# PortableShower.net
KiCad netlist of a schematic drawn in EAGLE
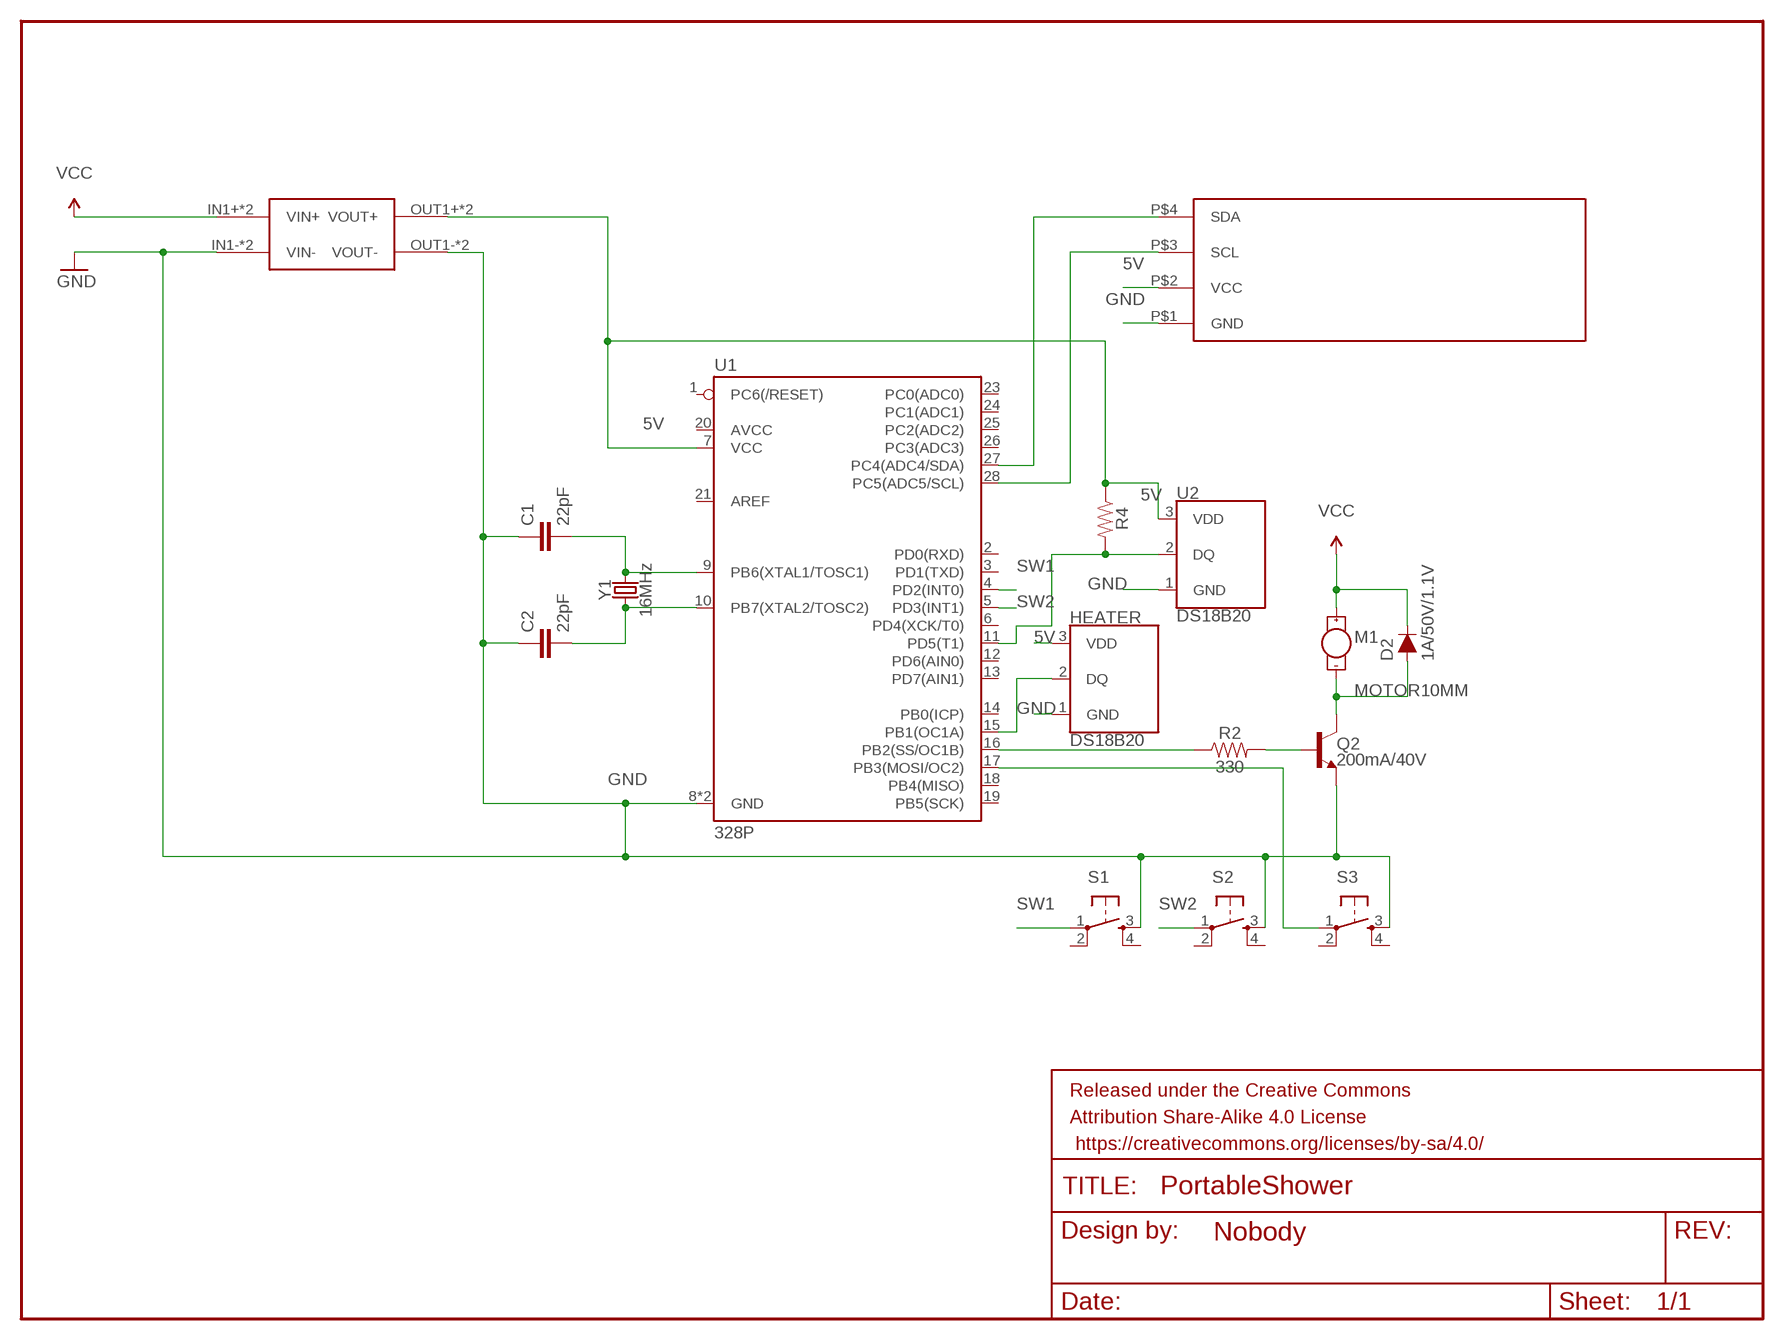
[diagram p0: schematic, sheet 1]

(export (version "E")
  (design (tool "Eeschema 10.0.6"))
  (components
    (comp (ref "C1")
      (value "22pF")
      (footprint "eagle-import:CAP-PTH-2.54")
      (libsource (lib "eagle-import") (part "22PF-PTH-2.54MM-200V-5%"))
    )
    (comp (ref "C2")
      (value "22pF")
      (footprint "eagle-import:CAP-PTH-2.54")
      (libsource (lib "eagle-import") (part "22PF-PTH-2.54MM-200V-5%"))
    )
    (comp (ref "D2")
      (value "1A/50V/1.1V")
      (footprint "eagle-import:DIODE-1N4001")
      (libsource (lib "eagle-import") (part "DIODE-PTH"))
    )
    (comp (ref "FRAME1")
      (value "FRAME-LETTERNO_PACKAGE")
      (footprint "eagle-import:DUMMY")
      (fields (field (name "DESIGNER") "Nobody"))
      (libsource (lib "eagle-import") (part "FRAME-LETTERNO_PACKAGE"))
    )
    (comp (ref "HEATER")
      (value "DS18B20")
      (footprint "eagle-import:TO-92-AMMO")
      (libsource (lib "eagle-import") (part "DS18B20"))
    )
    (comp (ref "M1")
      (value "MOTOR10MM")
      (footprint "eagle-import:VIBE-MOTOR-10MM")
      (libsource (lib "eagle-import") (part "MOTOR10MM"))
    )
    (comp (ref "OLED")
      (value "OLED")
      (footprint "eagle-import:SIP")
      (libsource (lib "eagle-import") (part "OLED"))
    )
    (comp (ref "Q2")
      (value "200mA/40V")
      (footprint "eagle-import:TO-92")
      (libsource (lib "eagle-import") (part "TRANS_NPN-2N3904"))
    )
    (comp (ref "R2")
      (value "330")
      (footprint "eagle-import:AXIAL-0.3")
      (libsource (lib "eagle-import") (part "330OHM-HORIZ-1/10W-5%"))
    )
    (comp (ref "R4")
      (value "RESISTORAXIAL-0.3")
      (footprint "eagle-import:AXIAL-0.3")
      (libsource (lib "eagle-import") (part "RESISTORAXIAL-0.3"))
    )
    (comp (ref "S1")
      (value "TAC_SWITCHPTH")
      (footprint "eagle-import:TACTILE-PTH")
      (libsource (lib "eagle-import") (part "TAC_SWITCHPTH"))
    )
    (comp (ref "S2")
      (value "TAC_SWITCHPTH")
      (footprint "eagle-import:TACTILE-PTH")
      (libsource (lib "eagle-import") (part "TAC_SWITCHPTH"))
    )
    (comp (ref "S3")
      (value "TAC_SWITCHPTH")
      (footprint "eagle-import:TACTILE-PTH")
      (libsource (lib "eagle-import") (part "TAC_SWITCHPTH"))
    )
    (comp (ref "U$1")
      (value "MP1584")
      (footprint "eagle-import:DC-BRICK")
      (libsource (lib "eagle-import") (part "MP1584"))
    )
    (comp (ref "U1")
      (value "328P")
      (footprint "eagle-import:DIP28")
      (libsource (lib "eagle-import") (part "ATMEGA328P_PDIP"))
    )
    (comp (ref "U2")
      (value "DS18B20")
      (footprint "eagle-import:TO-92-AMMO")
      (libsource (lib "eagle-import") (part "DS18B20"))
    )
    (comp (ref "Y1")
      (value "16MHz")
      (footprint "eagle-import:HC49US")
      (libsource (lib "eagle-import") (part "CRYSTAL-16MHZPTH-HC49US"))
    )
  )
  (nets
    (net (code "1") (name "/5V") (class "Default")
      (node (ref "HEATER") (pin "3") (pinfunction "VDD_3") (pintype "power_in"))
      (node (ref "OLED") (pin "P$2") (pinfunction "VCC_P$2") (pintype "bidirectional"))
      (node (ref "R4") (pin "P$1") (pinfunction "1_P$1") (pintype "passive"))
      (node (ref "U$1") (pin "OUT1+") (pinfunction "VOUT+_OUT1+") (pintype "output"))
      (node (ref "U$1") (pin "OUT2+") (pinfunction "VOUT+_OUT2+") (pintype "output"))
      (node (ref "U1") (pin "7") (pinfunction "VCC_7") (pintype "bidirectional"))
      (node (ref "U2") (pin "3") (pinfunction "VDD_3") (pintype "power_in"))
    )
    (net (code "2") (name "/SW1") (class "Default")
      (node (ref "S1") (pin "1") (pinfunction "1_1") (pintype "passive"))
      (node (ref "U1") (pin "4") (pinfunction "PD2(INT0)_4") (pintype "bidirectional"))
    )
    (net (code "3") (name "/SW2") (class "Default")
      (node (ref "S2") (pin "1") (pinfunction "1_1") (pintype "passive"))
      (node (ref "U1") (pin "5") (pinfunction "PD3(INT1)_5") (pintype "bidirectional"))
    )
    (net (code "4") (name "GND") (class "Default")
      (node (ref "C1") (pin "1") (pinfunction "1_1") (pintype "passive"))
      (node (ref "C2") (pin "1") (pinfunction "1_1") (pintype "passive"))
      (node (ref "HEATER") (pin "1") (pinfunction "GND_1") (pintype "power_in"))
      (node (ref "OLED") (pin "P$1") (pinfunction "GND_P$1") (pintype "bidirectional"))
      (node (ref "Q2") (pin "1") (pinfunction "E_1") (pintype "passive"))
      (node (ref "S1") (pin "3") (pinfunction "3_3") (pintype "passive"))
      (node (ref "S2") (pin "3") (pinfunction "3_3") (pintype "passive"))
      (node (ref "S3") (pin "3") (pinfunction "3_3") (pintype "passive"))
      (node (ref "U$1") (pin "IN1-") (pinfunction "VIN-_IN1-") (pintype "input"))
      (node (ref "U$1") (pin "IN2-") (pinfunction "VIN-_IN2-") (pintype "input"))
      (node (ref "U$1") (pin "OUT1-") (pinfunction "VOUT-_OUT1-") (pintype "output"))
      (node (ref "U$1") (pin "OUT2-") (pinfunction "VOUT-_OUT2-") (pintype "output"))
      (node (ref "U1") (pin "22") (pinfunction "GND_22") (pintype "bidirectional"))
      (node (ref "U1") (pin "8") (pinfunction "GND_8") (pintype "bidirectional"))
      (node (ref "U2") (pin "1") (pinfunction "GND_1") (pintype "power_in"))
    )
    (net (code "5") (name "Net-(HEATER-DQ)") (class "Default")
      (node (ref "HEATER") (pin "2") (pinfunction "DQ_2") (pintype "bidirectional"))
      (node (ref "U1") (pin "15") (pinfunction "PB1(OC1A)_15") (pintype "bidirectional"))
    )
    (net (code "6") (name "Net-(OLED-SCL)") (class "Default")
      (node (ref "OLED") (pin "P$3") (pinfunction "SCL_P$3") (pintype "bidirectional"))
      (node (ref "U1") (pin "28") (pinfunction "PC5(ADC5/SCL)_28") (pintype "bidirectional"))
    )
    (net (code "7") (name "Net-(OLED-SDA)") (class "Default")
      (node (ref "OLED") (pin "P$4") (pinfunction "SDA_P$4") (pintype "bidirectional"))
      (node (ref "U1") (pin "27") (pinfunction "PC4(ADC4/SDA)_27") (pintype "bidirectional"))
    )
    (net (code "8") (name "Net-(Q2-B)") (class "Default")
      (node (ref "Q2") (pin "2") (pinfunction "B_2") (pintype "passive"))
      (node (ref "R2") (pin "P$2") (pinfunction "2_P$2") (pintype "passive"))
    )
    (net (code "9") (name "Net-(Q2-C)") (class "Default")
      (node (ref "D2") (pin "A") (pinfunction "A_A") (pintype "passive"))
      (node (ref "M1") (pin "-") (pinfunction "-_-") (pintype "bidirectional"))
      (node (ref "Q2") (pin "3") (pinfunction "C_3") (pintype "passive"))
    )
    (net (code "10") (name "Net-(R2-1)") (class "Default")
      (node (ref "R2") (pin "P$1") (pinfunction "1_P$1") (pintype "passive"))
      (node (ref "U1") (pin "16") (pinfunction "PB2(SS/OC1B)_16") (pintype "bidirectional"))
    )
    (net (code "11") (name "Net-(R4-2)") (class "Default")
      (node (ref "R4") (pin "P$2") (pinfunction "2_P$2") (pintype "passive"))
      (node (ref "U1") (pin "11") (pinfunction "PD5(T1)_11") (pintype "bidirectional"))
      (node (ref "U2") (pin "2") (pinfunction "DQ_2") (pintype "bidirectional"))
    )
    (net (code "12") (name "Net-(U1-PB3(MOSI{slash}OC2))") (class "Default")
      (node (ref "S3") (pin "1") (pinfunction "1_1") (pintype "passive"))
      (node (ref "U1") (pin "17") (pinfunction "PB3(MOSI/OC2)_17") (pintype "bidirectional"))
    )
    (net (code "13") (name "Net-(U1-PB6(XTAL1{slash}TOSC1))") (class "Default")
      (node (ref "C1") (pin "2") (pinfunction "2_2") (pintype "passive"))
      (node (ref "U1") (pin "9") (pinfunction "PB6(XTAL1/TOSC1)_9") (pintype "bidirectional"))
      (node (ref "Y1") (pin "2") (pinfunction "2_2") (pintype "passive"))
    )
    (net (code "14") (name "Net-(U1-PB7(XTAL2{slash}TOSC2))") (class "Default")
      (node (ref "C2") (pin "2") (pinfunction "2_2") (pintype "passive"))
      (node (ref "U1") (pin "10") (pinfunction "PB7(XTAL2/TOSC2)_10") (pintype "bidirectional"))
      (node (ref "Y1") (pin "1") (pinfunction "1_1") (pintype "passive"))
    )
    (net (code "15") (name "VCC") (class "Default")
      (node (ref "D2") (pin "C") (pinfunction "C_C") (pintype "passive"))
      (node (ref "M1") (pin "+") (pinfunction "+_+") (pintype "bidirectional"))
      (node (ref "U$1") (pin "IN1+") (pinfunction "VIN+_IN1+") (pintype "input"))
      (node (ref "U$1") (pin "IN2+") (pinfunction "VIN+_IN2+") (pintype "input"))
    )
    (net (code "16") (name "unconnected-(S1-Pad2)") (class "Default")
      (node (ref "S1") (pin "2") (pinfunction "2_2") (pintype "passive"))
    )
    (net (code "17") (name "unconnected-(S1-Pad4)") (class "Default")
      (node (ref "S1") (pin "4") (pinfunction "4_4") (pintype "passive"))
    )
    (net (code "18") (name "unconnected-(S2-Pad2)") (class "Default")
      (node (ref "S2") (pin "2") (pinfunction "2_2") (pintype "passive"))
    )
    (net (code "19") (name "unconnected-(S2-Pad4)") (class "Default")
      (node (ref "S2") (pin "4") (pinfunction "4_4") (pintype "passive"))
    )
    (net (code "20") (name "unconnected-(S3-Pad2)") (class "Default")
      (node (ref "S3") (pin "2") (pinfunction "2_2") (pintype "passive"))
    )
    (net (code "21") (name "unconnected-(S3-Pad4)") (class "Default")
      (node (ref "S3") (pin "4") (pinfunction "4_4") (pintype "passive"))
    )
    (net (code "22") (name "unconnected-(U1-AREF-Pad21)") (class "Default")
      (node (ref "U1") (pin "21") (pinfunction "AREF_21") (pintype "bidirectional"))
    )
    (net (code "23") (name "unconnected-(U1-AVCC-Pad20)") (class "Default")
      (node (ref "U1") (pin "20") (pinfunction "AVCC_20") (pintype "bidirectional"))
    )
    (net (code "24") (name "unconnected-(U1-PB0(ICP)-Pad14)") (class "Default")
      (node (ref "U1") (pin "14") (pinfunction "PB0(ICP)_14") (pintype "bidirectional"))
    )
    (net (code "25") (name "unconnected-(U1-PB4(MISO)-Pad18)") (class "Default")
      (node (ref "U1") (pin "18") (pinfunction "PB4(MISO)_18") (pintype "bidirectional"))
    )
    (net (code "26") (name "unconnected-(U1-PB5(SCK)-Pad19)") (class "Default")
      (node (ref "U1") (pin "19") (pinfunction "PB5(SCK)_19") (pintype "bidirectional"))
    )
    (net (code "27") (name "unconnected-(U1-PC0(ADC0)-Pad23)") (class "Default")
      (node (ref "U1") (pin "23") (pinfunction "PC0(ADC0)_23") (pintype "bidirectional"))
    )
    (net (code "28") (name "unconnected-(U1-PC1(ADC1)-Pad24)") (class "Default")
      (node (ref "U1") (pin "24") (pinfunction "PC1(ADC1)_24") (pintype "bidirectional"))
    )
    (net (code "29") (name "unconnected-(U1-PC2(ADC2)-Pad25)") (class "Default")
      (node (ref "U1") (pin "25") (pinfunction "PC2(ADC2)_25") (pintype "bidirectional"))
    )
    (net (code "30") (name "unconnected-(U1-PC3(ADC3)-Pad26)") (class "Default")
      (node (ref "U1") (pin "26") (pinfunction "PC3(ADC3)_26") (pintype "bidirectional"))
    )
    (net (code "31") (name "unconnected-(U1-PC6({slash}RESET)-Pad1)") (class "Default")
      (node (ref "U1") (pin "1") (pinfunction "PC6(/RESET)_1") (pintype "bidirectional"))
    )
    (net (code "32") (name "unconnected-(U1-PD0(RXD)-Pad2)") (class "Default")
      (node (ref "U1") (pin "2") (pinfunction "PD0(RXD)_2") (pintype "bidirectional"))
    )
    (net (code "33") (name "unconnected-(U1-PD1(TXD)-Pad3)") (class "Default")
      (node (ref "U1") (pin "3") (pinfunction "PD1(TXD)_3") (pintype "bidirectional"))
    )
    (net (code "34") (name "unconnected-(U1-PD4(XCK{slash}T0)-Pad6)") (class "Default")
      (node (ref "U1") (pin "6") (pinfunction "PD4(XCK/T0)_6") (pintype "bidirectional"))
    )
    (net (code "35") (name "unconnected-(U1-PD6(AIN0)-Pad12)") (class "Default")
      (node (ref "U1") (pin "12") (pinfunction "PD6(AIN0)_12") (pintype "bidirectional"))
    )
    (net (code "36") (name "unconnected-(U1-PD7(AIN1)-Pad13)") (class "Default")
      (node (ref "U1") (pin "13") (pinfunction "PD7(AIN1)_13") (pintype "bidirectional"))
    )
  )
)
